# Labort_pegys_g_v1.net
KiCad netlist of a schematic drawn in Altium Designer
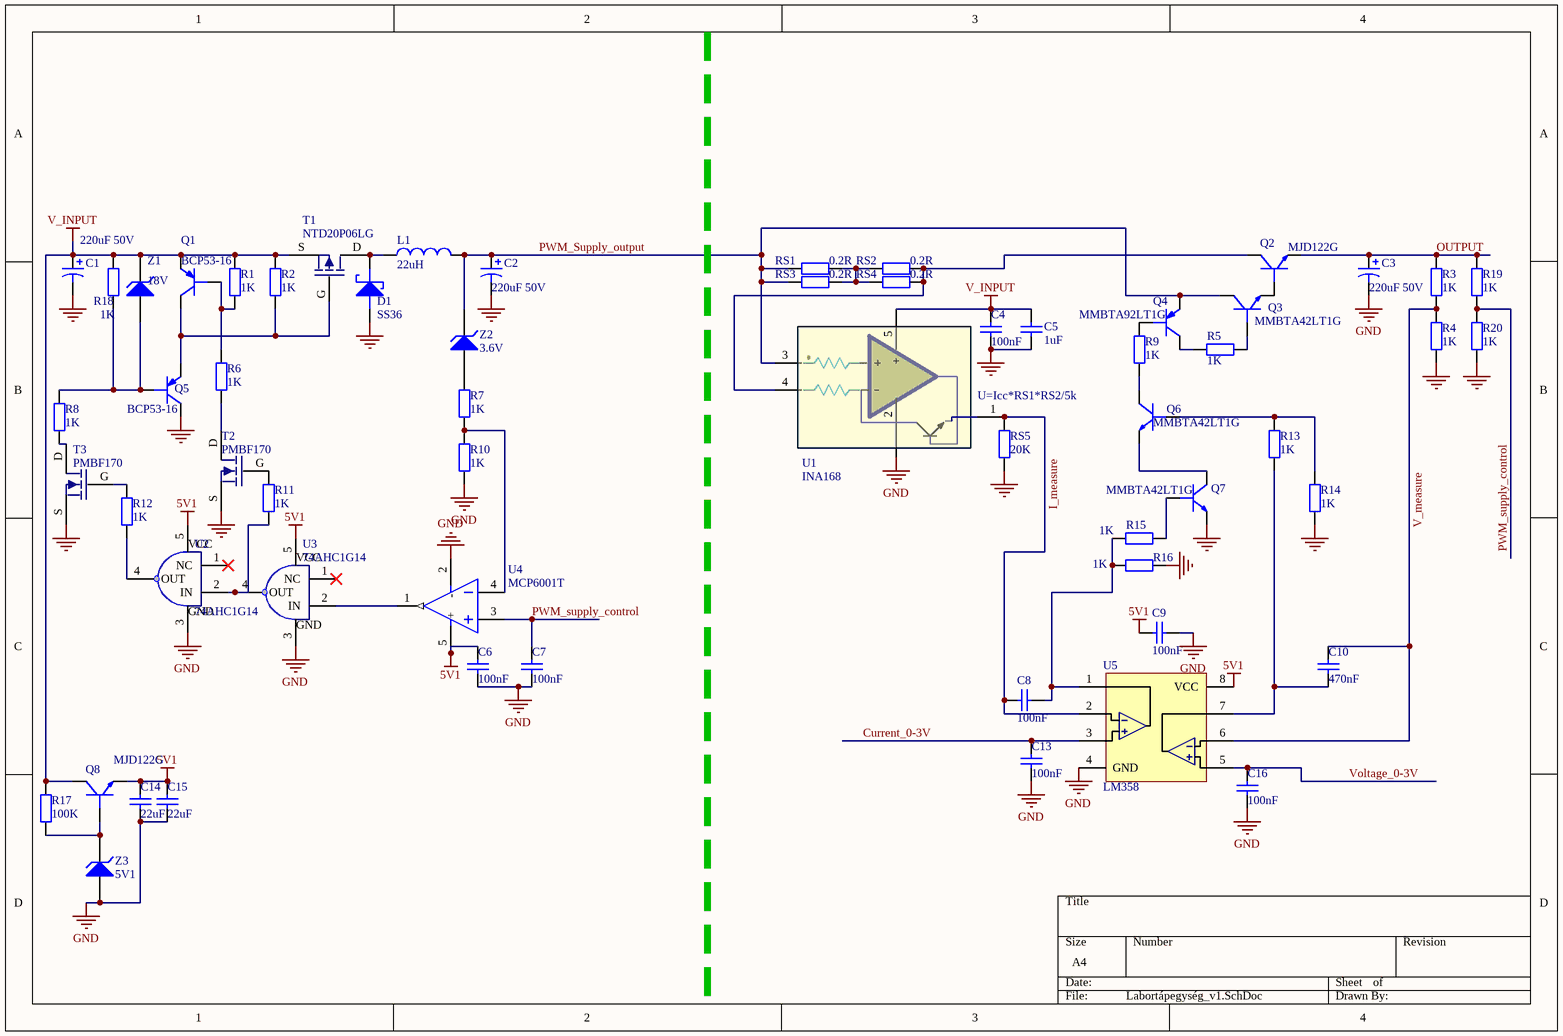
[diagram p0: Labortápegység_v1.SchDoc]

(export (version "E")
  (design (tool "Eeschema 10.0.6"))
  (components
    (comp (ref "C1")
      (value "220uF 50V")
      (footprint "CAP_ALU_ELKO_10D_10,5H")
      (description "Polarized Capacitor (Radial)")
      (libsource (lib "Miscellaneous Devices") (part "Cap Pol1"))
    )
    (comp (ref "C2")
      (value "220uF 50V")
      (footprint "CAP_ALU_ELKO_10D_10,5H")
      (description "Polarized Capacitor (Radial)")
      (libsource (lib "Miscellaneous Devices") (part "Cap Pol1"))
    )
    (comp (ref "C3")
      (value "220uF 50V")
      (footprint "CAP_ALU_ELKO_10D_10,5H")
      (description "Polarized Capacitor (Radial)")
      (libsource (lib "Miscellaneous Devices") (part "Cap Pol1"))
    )
    (comp (ref "C4")
      (value "100nF")
      (footprint "FP_0603_CAP_080")
      (description "Capacitor")
      (libsource (lib "Miscellaneous Devices") (part "Cap"))
    )
    (comp (ref "C5")
      (value "1uF")
      (footprint "FP_0603_CAP_080")
      (description "Capacitor")
      (libsource (lib "Capacitor") (part "CAP"))
    )
    (comp (ref "C6")
      (value "100nF")
      (footprint "FP_0603_CAP_080")
      (description "Capacitor")
      (libsource (lib "Miscellaneous Devices") (part "Cap"))
    )
    (comp (ref "C7")
      (value "100nF")
      (footprint "FP_0603_CAP_080")
      (description "Capacitor")
      (libsource (lib "Miscellaneous Devices") (part "Cap"))
    )
    (comp (ref "C8")
      (value "100nF")
      (footprint "FP_0603_CAP_080")
      (description "Capacitor")
      (libsource (lib "Miscellaneous Devices") (part "Cap"))
    )
    (comp (ref "C9")
      (value "100nF")
      (footprint "FP_0603_CAP_080")
      (description "Capacitor")
      (libsource (lib "Miscellaneous Devices") (part "Cap"))
    )
    (comp (ref "C10")
      (value "470nF")
      (footprint "FP_0603_CAP_080")
      (description "Capacitor")
      (libsource (lib "Miscellaneous Devices") (part "Cap"))
    )
    (comp (ref "C13")
      (value "100nF")
      (footprint "FP_0603_CAP_080")
      (description "Capacitor")
      (libsource (lib "Miscellaneous Devices") (part "Cap"))
    )
    (comp (ref "C14")
      (value "22uF")
      (footprint "FP_1210_CAP_N")
      (description "Capacitor")
      (libsource (lib "Capacitor") (part "CAP"))
    )
    (comp (ref "C15")
      (value "22uF")
      (footprint "FP_1210_CAP_N")
      (description "Capacitor")
      (libsource (lib "Capacitor") (part "CAP"))
    )
    (comp (ref "C16")
      (value "100nF")
      (footprint "FP_0603_CAP_080")
      (description "Capacitor")
      (libsource (lib "Miscellaneous Devices") (part "Cap"))
    )
    (comp (ref "D1")
      (value "SS36")
      (footprint "DIODE_SMC")
      (description "NXP - PMEG3020EJ,115 - SCHOTTKY RECT 30V 2A SOD323F")
      (libsource (lib "Diode") (part "SCHOTTKY"))
    )
    (comp (ref "L1")
      (value "22uH")
      (footprint "SRR1206_T")
      (description "Inductor")
      (libsource (lib "Miscellaneous Devices") (part "Inductor"))
    )
    (comp (ref "Q1")
      (value "BCP53-16")
      (footprint "TR_SOT223")
      (description "PNP General-purpose Transistor")
      (libsource (lib "Transistor") (part "PNP"))
    )
    (comp (ref "Q2")
      (value "MJD122G")
      (footprint "TR_D-PAK")
      (description "NPN General-purpose Transistor")
      (libsource (lib "Transistor") (part "NPN"))
    )
    (comp (ref "Q3")
      (value "MMBTA42LT1G")
      (footprint "TR_SOT23")
      (description "NPN General-purpose Transistor")
      (libsource (lib "Transistor") (part "NPN"))
    )
    (comp (ref "Q4")
      (value "MMBTA92LT1G")
      (footprint "TR_SOT23")
      (description "PNP General-purpose Transistor")
      (libsource (lib "Transistor") (part "PNP"))
    )
    (comp (ref "Q5")
      (value "BCP53-16")
      (footprint "TR_SOT223")
      (description "PNP General-purpose Transistor")
      (libsource (lib "Transistor") (part "PNP"))
    )
    (comp (ref "Q6")
      (value "MMBTA42LT1G")
      (footprint "TR_SOT23")
      (description "NPN General-purpose Transistor")
      (libsource (lib "Transistor") (part "NPN"))
    )
    (comp (ref "Q7")
      (value "MMBTA42LT1G")
      (footprint "TR_SOT23")
      (description "NPN General-purpose Transistor")
      (libsource (lib "Transistor") (part "NPN"))
    )
    (comp (ref "Q8")
      (value "MJD122G")
      (footprint "TR_D-PAK")
      (description "NPN General-purpose Transistor")
      (libsource (lib "Transistor") (part "NPN"))
    )
    (comp (ref "R1")
      (value "1K")
      (footprint "FP_0603_RES")
      (description "Resistor")
      (libsource (lib "") (part "RES_2"))
    )
    (comp (ref "R2")
      (value "1K")
      (footprint "FP_0603_RES")
      (description "Resistor")
      (libsource (lib "") (part "RES_2"))
    )
    (comp (ref "R3")
      (value "1K")
      (footprint "FP_0603_RES")
      (description "Resistor")
      (libsource (lib "") (part "RES_1"))
    )
    (comp (ref "R4")
      (value "1K")
      (footprint "FP_0603_RES")
      (description "Resistor")
      (libsource (lib "") (part "RES_1"))
    )
    (comp (ref "R5")
      (value "1K")
      (footprint "FP_0603_RES")
      (description "Resistor")
      (libsource (lib "Resistor") (part "RES"))
    )
    (comp (ref "R6")
      (value "1K")
      (footprint "FP_0603_RES")
      (description "Resistor")
      (libsource (lib "") (part "RES_1"))
    )
    (comp (ref "R7")
      (value "1K")
      (footprint "FP_0603_RES")
      (description "Resistor")
      (libsource (lib "") (part "RES_1"))
    )
    (comp (ref "R8")
      (value "1K")
      (footprint "FP_0603_RES")
      (description "Resistor")
      (libsource (lib "") (part "RES_1"))
    )
    (comp (ref "R9")
      (value "1K")
      (footprint "FP_0603_RES")
      (description "Resistor")
      (libsource (lib "") (part "RES_2"))
    )
    (comp (ref "R10")
      (value "1K")
      (footprint "FP_0603_RES")
      (description "Resistor")
      (libsource (lib "") (part "RES_1"))
    )
    (comp (ref "R11")
      (value "1K")
      (footprint "FP_0603_RES")
      (description "Resistor")
      (libsource (lib "") (part "RES_1"))
    )
    (comp (ref "R12")
      (value "1K")
      (footprint "FP_0603_RES")
      (description "Resistor")
      (libsource (lib "") (part "RES_1"))
    )
    (comp (ref "R13")
      (value "1K")
      (footprint "FP_0603_RES")
      (description "Resistor")
      (libsource (lib "") (part "RES_2"))
    )
    (comp (ref "R14")
      (value "1K")
      (footprint "FP_0603_RES")
      (description "Resistor")
      (libsource (lib "") (part "RES_1"))
    )
    (comp (ref "R15")
      (value "1K")
      (footprint "FP_0603_RES")
      (description "Resistor")
      (libsource (lib "") (part "RES_3"))
    )
    (comp (ref "R16")
      (value "1K")
      (footprint "FP_0603_RES")
      (description "Resistor")
      (libsource (lib "Resistor") (part "RES"))
    )
    (comp (ref "R17")
      (value "100K")
      (footprint "FP_0603_RES")
      (description "Resistor")
      (libsource (lib "Miscellaneous Devices") (part "Res3"))
    )
    (comp (ref "R18")
      (value "1K")
      (footprint "FP_0603_RES")
      (description "Resistor")
      (libsource (lib "") (part "RES_2"))
    )
    (comp (ref "R19")
      (value "1K")
      (footprint "FP_0603_RES")
      (description "Resistor")
      (libsource (lib "") (part "RES_1"))
    )
    (comp (ref "R20")
      (value "1K")
      (footprint "FP_0603_RES")
      (description "Resistor")
      (libsource (lib "") (part "RES_1"))
    )
    (comp (ref "RS1")
      (value "0.2R")
      (footprint "FP_2512_RES")
      (description "Resistor")
      (libsource (lib "") (part "Res3_1"))
    )
    (comp (ref "RS2")
      (value "0.2R")
      (footprint "FP_2512_RES")
      (description "Resistor")
      (libsource (lib "") (part "Res3_1"))
    )
    (comp (ref "RS3")
      (value "0.2R")
      (footprint "FP_2512_RES")
      (description "Resistor")
      (libsource (lib "") (part "Res3_1"))
    )
    (comp (ref "RS4")
      (value "0.2R")
      (footprint "FP_2512_RES")
      (description "Resistor")
      (libsource (lib "") (part "Res3_1"))
    )
    (comp (ref "RS5")
      (value "20K")
      (footprint "FP_0603_RES")
      (description "Resistor")
      (libsource (lib "Miscellaneous Devices") (part "Res3"))
    )
    (comp (ref "T1") (value "NTD20P06LG") (footprint "FET_D-PAK") (libsource (lib "FET") (part "PMOS")))
    (comp (ref "T2") (value "PMBF170") (footprint "FET_SOT23") (libsource (lib "FET") (part "NMOS")))
    (comp (ref "T3") (value "PMBF170") (footprint "FET_SOT23") (libsource (lib "FET") (part "NMOS")))
    (comp (ref "U1") (value "INA168") (footprint "ANALOG_SOT23-5") (libsource (lib "Analog") (part "INA168")))
    (comp (ref "U2")
      (value "74AHC1G14")
      (footprint "GATE_SOT23-5")
      (description "SCHMITT-TRIGGER INVERTER")
      (libsource (lib "Logic_gate") (part "74AHC1G14"))
    )
    (comp (ref "U3")
      (value "74AHC1G14")
      (footprint "GATE_SOT23-5")
      (description "SCHMITT-TRIGGER INVERTER")
      (libsource (lib "Logic_gate") (part "74AHC1G14"))
    )
    (comp (ref "U4")
      (value "MCP6001T")
      (footprint "ANALOG_SOT23-5")
      (libsource (lib "Analog") (part "MCP6001"))
    )
    (comp (ref "U5")
      (value "LM358")
      (footprint "FP_SO8_MS012AA")
      (description "Low power dual operational amplifiers")
      (libsource (lib "Analog") (part "LM358"))
    )
    (comp (ref "Z1")
      (value "18V")
      (footprint "SOD-80")
      (description "Zener Diode")
      (libsource (lib "Diode") (part "ZENER"))
    )
    (comp (ref "Z2")
      (value "3.6V")
      (footprint "SOD-80")
      (description "Zener Diode")
      (libsource (lib "Diode") (part "ZENER"))
    )
    (comp (ref "Z3")
      (value "5V1")
      (footprint "SOD-80")
      (description "Zener Diode")
      (libsource (lib "Diode") (part "ZENER"))
    )
  )
  (nets
    (net (code "1") (name "/Current_0-3V") (class "Default")
      (node (ref "C13") (pin "2") (pinfunction "2_2") (pintype "passive"))
      (node (ref "U5") (pin "3") (pintype "passive"))
    )
    (net (code "2") (name "/I_measure") (class "Default")
      (node (ref "C8") (pin "2") (pinfunction "2_2") (pintype "passive"))
      (node (ref "RS5") (pin "1") (pinfunction "1_1") (pintype "passive"))
      (node (ref "U1") (pin "1") (pinfunction "out_1") (pintype "passive"))
      (node (ref "U5") (pin "2") (pintype "passive"))
    )
    (net (code "3") (name "/OUTPUT") (class "Default")
      (node (ref "C3") (pin "P") (pinfunction "1_P") (pintype "passive"))
      (node (ref "Q2") (pin "E") (pinfunction "E_E") (pintype "passive"))
      (node (ref "R19") (pin "1") (pinfunction "1_1") (pintype "passive"))
      (node (ref "R3") (pin "1") (pinfunction "1_1") (pintype "passive"))
    )
    (net (code "4") (name "/PWM_Supply_output") (class "Default")
      (node (ref "C2") (pin "P") (pinfunction "1_P") (pintype "passive"))
      (node (ref "L1") (pin "2") (pinfunction "2_2") (pintype "passive"))
      (node (ref "Q3") (pin "C") (pinfunction "C_C") (pintype "passive"))
      (node (ref "Q4") (pin "E") (pinfunction "E_E") (pintype "passive"))
      (node (ref "RS1") (pin "1") (pinfunction "1_1") (pintype "passive"))
      (node (ref "RS3") (pin "1") (pinfunction "1_1") (pintype "passive"))
      (node (ref "U1") (pin "3") (pinfunction "+_3") (pintype "passive"))
      (node (ref "Z2") (pin "K") (pinfunction "K_K") (pintype "passive"))
    )
    (net (code "5") (name "/PWM_supply_control") (class "Default")
      (node (ref "C7") (pin "2") (pinfunction "2_2") (pintype "passive"))
      (node (ref "R19") (pin "2") (pinfunction "2_2") (pintype "passive"))
      (node (ref "R20") (pin "1") (pinfunction "1_1") (pintype "passive"))
      (node (ref "U4") (pin "3") (pinfunction "IN1+_3") (pintype "passive"))
    )
    (net (code "6") (name "/V_measure") (class "Default")
      (node (ref "C10") (pin "2") (pinfunction "2_2") (pintype "passive"))
      (node (ref "R3") (pin "2") (pinfunction "2_2") (pintype "passive"))
      (node (ref "R4") (pin "1") (pinfunction "1_1") (pintype "passive"))
      (node (ref "U5") (pin "6") (pintype "passive"))
    )
    (net (code "7") (name "/Voltage_0-3V") (class "Default")
      (node (ref "C16") (pin "2") (pinfunction "2_2") (pintype "passive"))
      (node (ref "U5") (pin "5") (pintype "passive"))
    )
    (net (code "8") (name "5V1") (class "Default")
      (node (ref "C14") (pin "2") (pinfunction "2_2") (pintype "passive"))
      (node (ref "C15") (pin "2") (pinfunction "2_2") (pintype "passive"))
      (node (ref "C6") (pin "2") (pinfunction "2_2") (pintype "passive"))
      (node (ref "C9") (pin "2") (pinfunction "2_2") (pintype "passive"))
      (node (ref "Q8") (pin "E") (pinfunction "E_E") (pintype "passive"))
      (node (ref "U2") (pin "5") (pinfunction "VCC_5") (pintype "passive"))
      (node (ref "U3") (pin "5") (pinfunction "VCC_5") (pintype "passive"))
      (node (ref "U4") (pin "5") (pinfunction "+_5") (pintype "power_in"))
      (node (ref "U5") (pin "8") (pinfunction "VCC_8") (pintype "passive"))
    )
    (net (code "9") (name "GND") (class "Default")
      (node (ref "C1") (pin "N") (pinfunction "2_N") (pintype "passive"))
      (node (ref "C13") (pin "1") (pinfunction "1_1") (pintype "passive"))
      (node (ref "C14") (pin "1") (pinfunction "1_1") (pintype "passive"))
      (node (ref "C15") (pin "1") (pinfunction "1_1") (pintype "passive"))
      (node (ref "C16") (pin "1") (pinfunction "1_1") (pintype "passive"))
      (node (ref "C2") (pin "N") (pinfunction "2_N") (pintype "passive"))
      (node (ref "C3") (pin "N") (pinfunction "2_N") (pintype "passive"))
      (node (ref "C4") (pin "1") (pinfunction "1_1") (pintype "passive"))
      (node (ref "C5") (pin "2") (pinfunction "2_2") (pintype "passive"))
      (node (ref "C6") (pin "1") (pinfunction "1_1") (pintype "passive"))
      (node (ref "C7") (pin "1") (pinfunction "1_1") (pintype "passive"))
      (node (ref "C9") (pin "1") (pinfunction "1_1") (pintype "passive"))
      (node (ref "D1") (pin "A") (pinfunction "A_A") (pintype "passive"))
      (node (ref "Q5") (pin "C") (pinfunction "C_C") (pintype "passive"))
      (node (ref "Q7") (pin "E") (pinfunction "E_E") (pintype "passive"))
      (node (ref "R10") (pin "2") (pinfunction "2_2") (pintype "passive"))
      (node (ref "R14") (pin "2") (pinfunction "2_2") (pintype "passive"))
      (node (ref "R16") (pin "2") (pinfunction "2_2") (pintype "passive"))
      (node (ref "R20") (pin "2") (pinfunction "2_2") (pintype "passive"))
      (node (ref "R4") (pin "2") (pinfunction "2_2") (pintype "passive"))
      (node (ref "RS5") (pin "2") (pinfunction "2_2") (pintype "passive"))
      (node (ref "T2") (pin "S") (pinfunction "S_S") (pintype "passive"))
      (node (ref "T3") (pin "S") (pinfunction "S_S") (pintype "passive"))
      (node (ref "U1") (pin "2") (pinfunction "V-_2") (pintype "passive"))
      (node (ref "U2") (pin "3") (pinfunction "GND_3") (pintype "passive"))
      (node (ref "U3") (pin "3") (pinfunction "GND_3") (pintype "passive"))
      (node (ref "U4") (pin "2") (pinfunction "-_2") (pintype "power_in"))
      (node (ref "U5") (pin "4") (pinfunction "GND_4") (pintype "passive"))
      (node (ref "Z3") (pin "A") (pinfunction "A_A") (pintype "passive"))
    )
    (net (code "10") (name "Net-(C8-Pad1)") (class "Default")
      (node (ref "C8") (pin "1") (pinfunction "1_1") (pintype "passive"))
      (node (ref "R15") (pin "2") (pinfunction "2_2") (pintype "passive"))
      (node (ref "R16") (pin "1") (pinfunction "1_1") (pintype "passive"))
      (node (ref "U5") (pin "1") (pintype "passive"))
    )
    (net (code "11") (name "Net-(C10-Pad1)") (class "Default")
      (node (ref "C10") (pin "1") (pinfunction "1_1") (pintype "passive"))
      (node (ref "R13") (pin "1") (pinfunction "1_1") (pintype "passive"))
      (node (ref "U5") (pin "7") (pintype "passive"))
    )
    (net (code "12") (name "Net-(D1-PadK)") (class "Default")
      (node (ref "D1") (pin "K") (pinfunction "K_K") (pintype "passive"))
      (node (ref "L1") (pin "1") (pinfunction "1_1") (pintype "passive"))
      (node (ref "T1") (pin "D") (pinfunction "D_D") (pintype "passive"))
    )
    (net (code "13") (name "Net-(Q1-PadB)") (class "Default")
      (node (ref "Q1") (pin "B") (pinfunction "B_B") (pintype "passive"))
      (node (ref "R1") (pin "1") (pinfunction "1_1") (pintype "passive"))
      (node (ref "R6") (pin "1") (pinfunction "1_1") (pintype "passive"))
    )
    (net (code "14") (name "Net-(Q1-PadC)") (class "Default")
      (node (ref "Q1") (pin "C") (pinfunction "C_C") (pintype "passive"))
      (node (ref "Q5") (pin "E") (pinfunction "E_E") (pintype "passive"))
      (node (ref "R2") (pin "1") (pinfunction "1_1") (pintype "passive"))
      (node (ref "T1") (pin "G") (pinfunction "G_G") (pintype "passive"))
    )
    (net (code "15") (name "Net-(Q2-PadB)") (class "Default")
      (node (ref "Q2") (pin "B") (pinfunction "B_B") (pintype "passive"))
      (node (ref "Q3") (pin "E") (pinfunction "E_E") (pintype "passive"))
    )
    (net (code "16") (name "Net-(Q3-PadB)") (class "Default")
      (node (ref "Q3") (pin "B") (pinfunction "B_B") (pintype "passive"))
      (node (ref "R5") (pin "2") (pinfunction "2_2") (pintype "passive"))
    )
    (net (code "17") (name "Net-(Q4-PadB)") (class "Default")
      (node (ref "Q4") (pin "B") (pinfunction "B_B") (pintype "passive"))
      (node (ref "R9") (pin "2") (pinfunction "2_2") (pintype "passive"))
    )
    (net (code "18") (name "Net-(Q4-PadC)") (class "Default")
      (node (ref "Q4") (pin "C") (pinfunction "C_C") (pintype "passive"))
      (node (ref "R5") (pin "1") (pinfunction "1_1") (pintype "passive"))
    )
    (net (code "19") (name "Net-(Q5-PadB)") (class "Default")
      (node (ref "Q5") (pin "B") (pinfunction "B_B") (pintype "passive"))
      (node (ref "R18") (pin "1") (pinfunction "1_1") (pintype "passive"))
      (node (ref "R8") (pin "1") (pinfunction "1_1") (pintype "passive"))
      (node (ref "Z1") (pin "A") (pinfunction "A_A") (pintype "passive"))
    )
    (net (code "20") (name "Net-(Q6-PadB)") (class "Default")
      (node (ref "Q6") (pin "B") (pinfunction "B_B") (pintype "passive"))
      (node (ref "R13") (pin "2") (pinfunction "2_2") (pintype "passive"))
      (node (ref "R14") (pin "1") (pinfunction "1_1") (pintype "passive"))
    )
    (net (code "21") (name "Net-(Q6-PadC)") (class "Default")
      (node (ref "Q6") (pin "C") (pinfunction "C_C") (pintype "passive"))
      (node (ref "R9") (pin "1") (pinfunction "1_1") (pintype "passive"))
    )
    (net (code "22") (name "Net-(Q6-PadE)") (class "Default")
      (node (ref "Q6") (pin "E") (pinfunction "E_E") (pintype "passive"))
      (node (ref "Q7") (pin "C") (pinfunction "C_C") (pintype "passive"))
    )
    (net (code "23") (name "Net-(Q7-PadB)") (class "Default")
      (node (ref "Q7") (pin "B") (pinfunction "B_B") (pintype "passive"))
      (node (ref "R15") (pin "1") (pinfunction "1_1") (pintype "passive"))
    )
    (net (code "24") (name "Net-(Q8-PadB)") (class "Default")
      (node (ref "Q8") (pin "B") (pinfunction "B_B") (pintype "passive"))
      (node (ref "R17") (pin "2") (pinfunction "2_2") (pintype "passive"))
      (node (ref "Z3") (pin "K") (pinfunction "K_K") (pintype "passive"))
    )
    (net (code "25") (name "Net-(R6-Pad2)") (class "Default")
      (node (ref "R6") (pin "2") (pinfunction "2_2") (pintype "passive"))
      (node (ref "T2") (pin "D") (pinfunction "D_D") (pintype "passive"))
    )
    (net (code "26") (name "Net-(R7-Pad1)") (class "Default")
      (node (ref "R7") (pin "1") (pinfunction "1_1") (pintype "passive"))
      (node (ref "Z2") (pin "A") (pinfunction "A_A") (pintype "passive"))
    )
    (net (code "27") (name "Net-(R8-Pad2)") (class "Default")
      (node (ref "R8") (pin "2") (pinfunction "2_2") (pintype "passive"))
      (node (ref "T3") (pin "D") (pinfunction "D_D") (pintype "passive"))
    )
    (net (code "28") (name "Net-(R11-Pad1)") (class "Default")
      (node (ref "R11") (pin "1") (pinfunction "1_1") (pintype "passive"))
      (node (ref "T2") (pin "G") (pinfunction "G_G") (pintype "passive"))
    )
    (net (code "29") (name "Net-(R12-Pad1)") (class "Default")
      (node (ref "R12") (pin "1") (pinfunction "1_1") (pintype "passive"))
      (node (ref "T3") (pin "G") (pinfunction "G_G") (pintype "passive"))
    )
    (net (code "30") (name "Net-(RS1-Pad2)") (class "Default")
      (node (ref "RS1") (pin "2") (pinfunction "2_2") (pintype "passive"))
      (node (ref "RS2") (pin "1") (pinfunction "1_1") (pintype "passive"))
      (node (ref "RS3") (pin "2") (pinfunction "2_2") (pintype "passive"))
      (node (ref "RS4") (pin "1") (pinfunction "1_1") (pintype "passive"))
    )
    (net (code "31") (name "Net-(U1--)") (class "Default")
      (node (ref "Q2") (pin "C") (pinfunction "C_C") (pintype "passive"))
      (node (ref "RS2") (pin "2") (pinfunction "2_2") (pintype "passive"))
      (node (ref "RS4") (pin "2") (pinfunction "2_2") (pintype "passive"))
      (node (ref "U1") (pin "4") (pinfunction "-_4") (pintype "passive"))
    )
    (net (code "32") (name "Net-(U2-IN)") (class "Default")
      (node (ref "R11") (pin "2") (pinfunction "2_2") (pintype "passive"))
      (node (ref "U2") (pin "2") (pinfunction "IN_2") (pintype "passive"))
      (node (ref "U3") (pin "4") (pinfunction "OUT_4") (pintype "passive"))
    )
    (net (code "33") (name "Net-(U2-OUT)") (class "Default")
      (node (ref "R12") (pin "2") (pinfunction "2_2") (pintype "passive"))
      (node (ref "U2") (pin "4") (pinfunction "OUT_4") (pintype "passive"))
    )
    (net (code "34") (name "Net-(U3-IN)") (class "Default")
      (node (ref "U3") (pin "2") (pinfunction "IN_2") (pintype "passive"))
      (node (ref "U4") (pin "1") (pinfunction "OUT1_1") (pintype "output"))
    )
    (net (code "35") (name "Net-(U4-IN1-)") (class "Default")
      (node (ref "R10") (pin "1") (pinfunction "1_1") (pintype "passive"))
      (node (ref "R7") (pin "2") (pinfunction "2_2") (pintype "passive"))
      (node (ref "U4") (pin "4") (pinfunction "IN1-_4") (pintype "passive"))
    )
    (net (code "36") (name "V_INPUT") (class "Default")
      (node (ref "C1") (pin "P") (pinfunction "1_P") (pintype "passive"))
      (node (ref "C4") (pin "2") (pinfunction "2_2") (pintype "passive"))
      (node (ref "C5") (pin "1") (pinfunction "1_1") (pintype "passive"))
      (node (ref "Q1") (pin "E") (pinfunction "E_E") (pintype "passive"))
      (node (ref "Q8") (pin "C") (pinfunction "C_C") (pintype "passive"))
      (node (ref "R1") (pin "2") (pinfunction "2_2") (pintype "passive"))
      (node (ref "R17") (pin "1") (pinfunction "1_1") (pintype "passive"))
      (node (ref "R18") (pin "2") (pinfunction "2_2") (pintype "passive"))
      (node (ref "R2") (pin "2") (pinfunction "2_2") (pintype "passive"))
      (node (ref "T1") (pin "S") (pinfunction "S_S") (pintype "passive"))
      (node (ref "U1") (pin "5") (pinfunction "+_5") (pintype "passive"))
      (node (ref "Z1") (pin "K") (pinfunction "K_K") (pintype "passive"))
    )
    (net (code "37") (name "unconnected-(U1-NC-Pad8)") (class "Default")
      (node (ref "U1") (pin "8") (pinfunction "NC_8") (pintype "passive"))
    )
    (net (code "38") (name "unconnected-(U2-NC-Pad1)") (class "Default")
      (node (ref "U2") (pin "1") (pinfunction "NC_1") (pintype "passive+no_connect"))
    )
    (net (code "39") (name "unconnected-(U3-NC-Pad1)") (class "Default")
      (node (ref "U3") (pin "1") (pinfunction "NC_1") (pintype "passive+no_connect"))
    )
  )
)
